# I2C0_Mux.net
KiCad netlist of a schematic drawn in Altium Designer
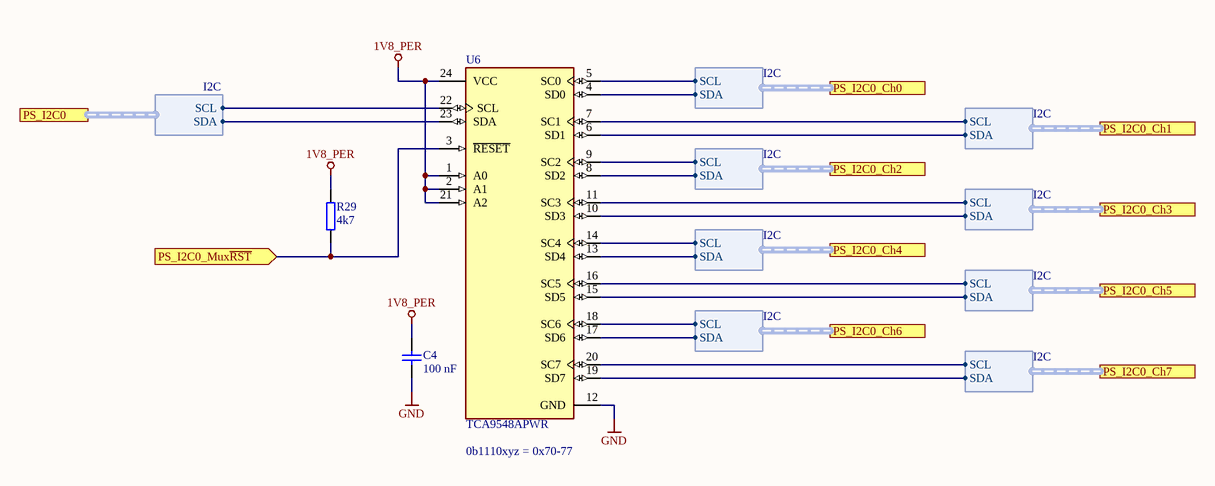
[diagram p0: I2C0_Mux.SchDoc]

(export (version "E")
  (design (tool "Eeschema 10.0.6"))
  (components
    (comp (ref "C4")
      (value "100 nF")
      (footprint "C_0603_TE")
      (description "Generic capacitor")
      (fields
        (field (name "MANUFACTURER PART NUMBER") "UZgen_C_0603_100nF_50V_X7R")
        (field (name "MANUFACTURER") "UZgen")
        (field (name "CREATED FROM") "AGeiger")
      )
      (libsource (lib "user") (part "CAP-NP"))
    )
    (comp (ref "R29")
      (value "4k7")
      (footprint "R_0603_TE")
      (description "Generic resistor")
      (fields
        (field (name "MANUFACTURER PART NUMBER") "UZgen_R_0603_4k7")
        (field (name "MANUFACTURER") "UZgen")
        (field (name "CREATED FROM") "UZgenTool")
      )
      (libsource (lib "user") (part "RES"))
    )
    (comp (ref "U6")
      (value "TCA9548APWR")
      (footprint "FP-PW0024A-IPC_A")
      (description "Switch ICs - Various 8-Channel I2C Switch")
      (fields
        (field (name "MANUFACTURER") "Texas Instruments")
        (field (name "LCSC PART NUMBER") "C130026")
        (field (name "CREATED FROM") "FRosner")
      )
      (libsource (lib "user") (part "TCA9458A"))
    )
  )
  (nets
    (net (code "2") (name "/PS_I2C0_Mux~{RST}") (class "Default")
      (node (ref "R29") (pin "1") (pinfunction "1_1") (pintype "passive"))
      (node (ref "U6") (pin "3") (pinfunction "~{RESET}_3") (pintype "input"))
    )
    (net (code "4") (name "1V8_PER") (class "Default")
      (node (ref "C4") (pin "2") (pinfunction "2_2") (pintype "passive"))
      (node (ref "R29") (pin "2") (pinfunction "2_2") (pintype "passive"))
      (node (ref "U6") (pin "1") (pinfunction "A0_1") (pintype "input"))
      (node (ref "U6") (pin "2") (pinfunction "A1_2") (pintype "input"))
      (node (ref "U6") (pin "21") (pinfunction "A2_21") (pintype "input"))
      (node (ref "U6") (pin "24") (pinfunction "VCC_24") (pintype "power_in"))
    )
    (net (code "5") (name "GND") (class "Default")
      (node (ref "C4") (pin "1") (pinfunction "1_1") (pintype "passive"))
      (node (ref "U6") (pin "12") (pinfunction "GND_12") (pintype "power_in"))
    )
    (net (code "6") (name "unconnected-(U6-SC0-Pad5)") (class "Default")
      (node (ref "U6") (pin "5") (pinfunction "SC0_5") (pintype "bidirectional"))
    )
    (net (code "7") (name "unconnected-(U6-SC1-Pad7)") (class "Default")
      (node (ref "U6") (pin "7") (pinfunction "SC1_7") (pintype "bidirectional"))
    )
    (net (code "8") (name "unconnected-(U6-SC2-Pad9)") (class "Default")
      (node (ref "U6") (pin "9") (pinfunction "SC2_9") (pintype "bidirectional"))
    )
    (net (code "9") (name "unconnected-(U6-SC3-Pad11)") (class "Default")
      (node (ref "U6") (pin "11") (pinfunction "SC3_11") (pintype "bidirectional"))
    )
    (net (code "10") (name "unconnected-(U6-SC4-Pad14)") (class "Default")
      (node (ref "U6") (pin "14") (pinfunction "SC4_14") (pintype "bidirectional"))
    )
    (net (code "11") (name "unconnected-(U6-SC5-Pad16)") (class "Default")
      (node (ref "U6") (pin "16") (pinfunction "SC5_16") (pintype "bidirectional"))
    )
    (net (code "12") (name "unconnected-(U6-SC6-Pad18)") (class "Default")
      (node (ref "U6") (pin "18") (pinfunction "SC6_18") (pintype "bidirectional"))
    )
    (net (code "13") (name "unconnected-(U6-SC7-Pad20)") (class "Default")
      (node (ref "U6") (pin "20") (pinfunction "SC7_20") (pintype "bidirectional"))
    )
    (net (code "14") (name "unconnected-(U6-SCL-Pad22)") (class "Default")
      (node (ref "U6") (pin "22") (pinfunction "SCL_22") (pintype "bidirectional"))
    )
    (net (code "15") (name "unconnected-(U6-SD0-Pad4)") (class "Default")
      (node (ref "U6") (pin "4") (pinfunction "SD0_4") (pintype "bidirectional"))
    )
    (net (code "16") (name "unconnected-(U6-SD1-Pad6)") (class "Default")
      (node (ref "U6") (pin "6") (pinfunction "SD1_6") (pintype "bidirectional"))
    )
    (net (code "17") (name "unconnected-(U6-SD2-Pad8)") (class "Default")
      (node (ref "U6") (pin "8") (pinfunction "SD2_8") (pintype "bidirectional"))
    )
    (net (code "18") (name "unconnected-(U6-SD3-Pad10)") (class "Default")
      (node (ref "U6") (pin "10") (pinfunction "SD3_10") (pintype "bidirectional"))
    )
    (net (code "19") (name "unconnected-(U6-SD4-Pad13)") (class "Default")
      (node (ref "U6") (pin "13") (pinfunction "SD4_13") (pintype "bidirectional"))
    )
    (net (code "20") (name "unconnected-(U6-SD5-Pad15)") (class "Default")
      (node (ref "U6") (pin "15") (pinfunction "SD5_15") (pintype "bidirectional"))
    )
    (net (code "21") (name "unconnected-(U6-SD6-Pad17)") (class "Default")
      (node (ref "U6") (pin "17") (pinfunction "SD6_17") (pintype "bidirectional"))
    )
    (net (code "22") (name "unconnected-(U6-SD7-Pad19)") (class "Default")
      (node (ref "U6") (pin "19") (pinfunction "SD7_19") (pintype "bidirectional"))
    )
    (net (code "23") (name "unconnected-(U6-SDA-Pad23)") (class "Default")
      (node (ref "U6") (pin "23") (pinfunction "SDA_23") (pintype "bidirectional"))
    )
  )
)
